# attiny4313_bo.net
KiCad netlist of a schematic drawn in EAGLE
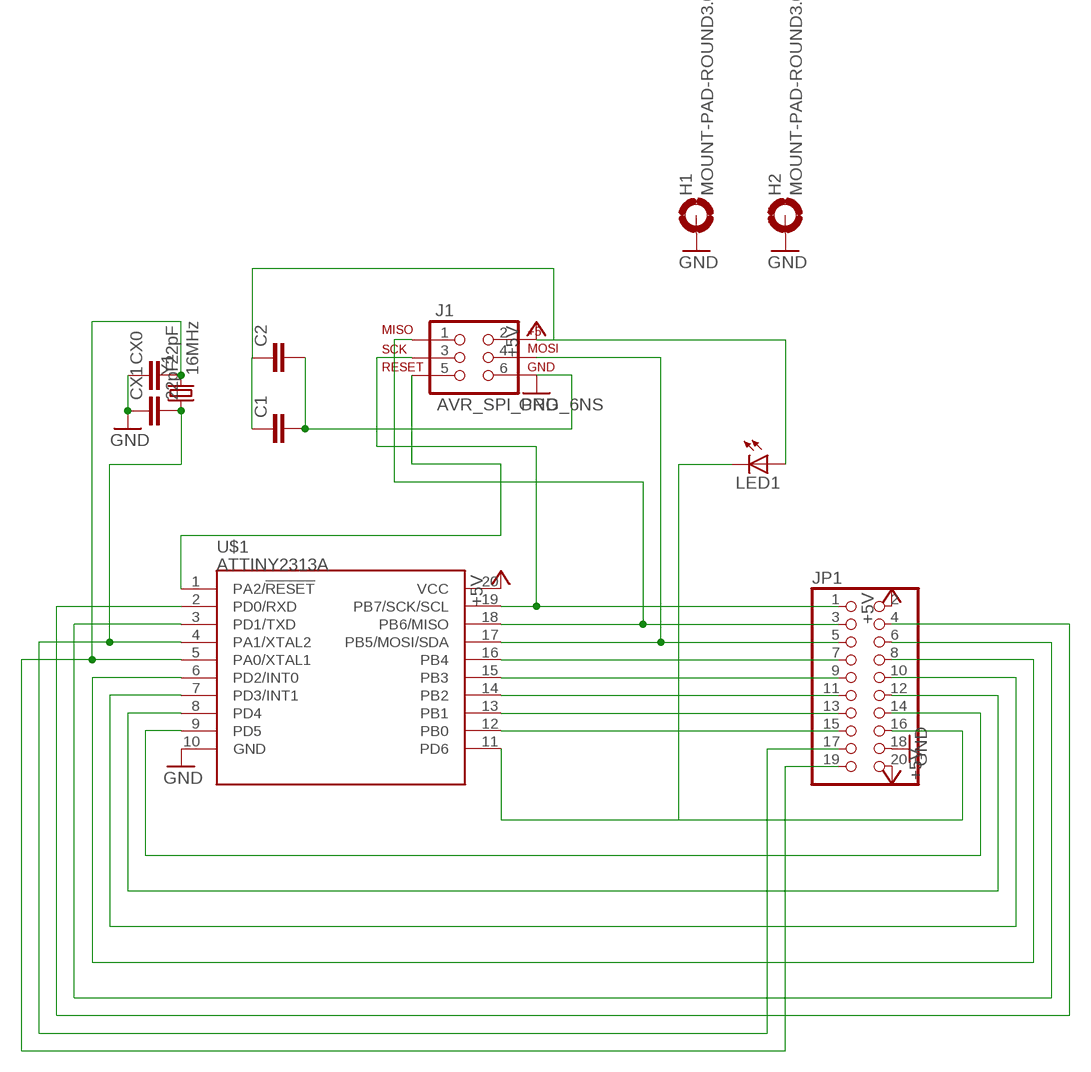
[diagram p0: schematic, sheet 1]

(export (version "E")
  (design (tool "Eeschema 10.0.6"))
  (components
    (comp (ref "C1")
      (value "C-EUC0805")
      (footprint "eagle-import:C0805")
      (libsource (lib "eagle-import") (part "C-EUC0805"))
    )
    (comp (ref "C2")
      (value "C-EUC0805")
      (footprint "eagle-import:C0805")
      (libsource (lib "eagle-import") (part "C-EUC0805"))
    )
    (comp (ref "CX0")
      (value "22pF")
      (footprint "eagle-import:C0603")
      (libsource (lib "eagle-import") (part "C-EUC0603"))
    )
    (comp (ref "CX1")
      (value "22pF")
      (footprint "eagle-import:C0603")
      (libsource (lib "eagle-import") (part "C-EUC0603"))
    )
    (comp (ref "H1")
      (value "MOUNT-PAD-ROUND3.0")
      (footprint "eagle-import:3,0-PAD")
      (libsource (lib "eagle-import") (part "MOUNT-PAD-ROUND3.0"))
    )
    (comp (ref "H2")
      (value "MOUNT-PAD-ROUND3.0")
      (footprint "eagle-import:3,0-PAD")
      (libsource (lib "eagle-import") (part "MOUNT-PAD-ROUND3.0"))
    )
    (comp (ref "J1")
      (value "AVR_SPI_PRG_6NS")
      (footprint "eagle-import:2X3-NS")
      (libsource (lib "eagle-import") (part "AVR_SPI_PRG_6NS"))
    )
    (comp (ref "JP1")
      (value "PINHD-2X10")
      (footprint "eagle-import:2X10")
      (libsource (lib "eagle-import") (part "PINHD-2X10"))
    )
    (comp (ref "LED1")
      (value "LED0603")
      (footprint "eagle-import:LED-0603")
      (libsource (lib "eagle-import") (part "LED0603"))
    )
    (comp (ref "U$1")
      (value "ATTINY2313A")
      (footprint "eagle-import:SOP20")
      (libsource (lib "eagle-import") (part "ATTINY2313A"))
    )
    (comp (ref "Y1")
      (value "16MHz")
      (footprint "eagle-import:CRYSTAL-SMD-5X3")
      (libsource (lib "eagle-import") (part "CRYSTAL5X3"))
    )
  )
  (nets
    (net (code "1") (name "+5V") (class "Default")
      (node (ref "C1") (pin "1") (pinfunction "1_1") (pintype "passive"))
      (node (ref "C2") (pin "1") (pinfunction "1_1") (pintype "passive"))
      (node (ref "J1") (pin "2") (pinfunction "2_2") (pintype "passive"))
      (node (ref "JP1") (pin "2") (pinfunction "2_2") (pintype "passive"))
      (node (ref "JP1") (pin "20") (pinfunction "20_20") (pintype "passive"))
      (node (ref "LED1") (pin "A") (pinfunction "A_A") (pintype "passive"))
      (node (ref "U$1") (pin "20") (pinfunction "VCC_20") (pintype "bidirectional"))
    )
    (net (code "2") (name "GND") (class "Default")
      (node (ref "C1") (pin "2") (pinfunction "2_2") (pintype "passive"))
      (node (ref "C2") (pin "2") (pinfunction "2_2") (pintype "passive"))
      (node (ref "CX0") (pin "1") (pinfunction "1_1") (pintype "passive"))
      (node (ref "CX1") (pin "1") (pinfunction "1_1") (pintype "passive"))
      (node (ref "H1") (pin "B3,0") (pinfunction "MOUNT_B3,0") (pintype "passive"))
      (node (ref "H2") (pin "B3,0") (pinfunction "MOUNT_B3,0") (pintype "passive"))
      (node (ref "J1") (pin "6") (pinfunction "6_6") (pintype "passive"))
      (node (ref "JP1") (pin "18") (pinfunction "18_18") (pintype "passive"))
      (node (ref "U$1") (pin "10") (pinfunction "GND_10") (pintype "bidirectional"))
    )
    (net (code "3") (name "Net-(U$1-PA0{slash}XTAL1)") (class "Default")
      (node (ref "CX0") (pin "2") (pinfunction "2_2") (pintype "passive"))
      (node (ref "JP1") (pin "19") (pinfunction "19_19") (pintype "passive"))
      (node (ref "U$1") (pin "5") (pinfunction "PA0/XTAL1_5") (pintype "bidirectional"))
      (node (ref "Y1") (pin "3") (pinfunction "2_3") (pintype "passive"))
    )
    (net (code "4") (name "Net-(U$1-PA1{slash}XTAL2)") (class "Default")
      (node (ref "CX1") (pin "2") (pinfunction "2_2") (pintype "passive"))
      (node (ref "JP1") (pin "17") (pinfunction "17_17") (pintype "passive"))
      (node (ref "U$1") (pin "4") (pinfunction "PA1/XTAL2_4") (pintype "bidirectional"))
      (node (ref "Y1") (pin "1") (pinfunction "1_1") (pintype "passive"))
    )
    (net (code "5") (name "Net-(U$1-PA2{slash}~{RESET})") (class "Default")
      (node (ref "J1") (pin "5") (pinfunction "5_5") (pintype "passive"))
      (node (ref "U$1") (pin "1") (pinfunction "PA2/~{RESET}_1") (pintype "bidirectional"))
    )
    (net (code "6") (name "Net-(U$1-PB0)") (class "Default")
      (node (ref "JP1") (pin "15") (pinfunction "15_15") (pintype "passive"))
      (node (ref "U$1") (pin "12") (pinfunction "PB0_12") (pintype "bidirectional"))
    )
    (net (code "7") (name "Net-(U$1-PB1)") (class "Default")
      (node (ref "JP1") (pin "13") (pinfunction "13_13") (pintype "passive"))
      (node (ref "U$1") (pin "13") (pinfunction "PB1_13") (pintype "bidirectional"))
    )
    (net (code "8") (name "Net-(U$1-PB2)") (class "Default")
      (node (ref "JP1") (pin "11") (pinfunction "11_11") (pintype "passive"))
      (node (ref "U$1") (pin "14") (pinfunction "PB2_14") (pintype "bidirectional"))
    )
    (net (code "9") (name "Net-(U$1-PB3)") (class "Default")
      (node (ref "JP1") (pin "9") (pinfunction "9_9") (pintype "passive"))
      (node (ref "U$1") (pin "15") (pinfunction "PB3_15") (pintype "bidirectional"))
    )
    (net (code "10") (name "Net-(U$1-PB4)") (class "Default")
      (node (ref "JP1") (pin "7") (pinfunction "7_7") (pintype "passive"))
      (node (ref "U$1") (pin "16") (pinfunction "PB4_16") (pintype "bidirectional"))
    )
    (net (code "11") (name "Net-(U$1-PB5{slash}MOSI{slash}SDA)") (class "Default")
      (node (ref "J1") (pin "4") (pinfunction "4_4") (pintype "passive"))
      (node (ref "JP1") (pin "5") (pinfunction "5_5") (pintype "passive"))
      (node (ref "U$1") (pin "17") (pinfunction "PB5/MOSI/SDA_17") (pintype "bidirectional"))
    )
    (net (code "12") (name "Net-(U$1-PB6{slash}MISO)") (class "Default")
      (node (ref "J1") (pin "1") (pinfunction "1_1") (pintype "passive"))
      (node (ref "JP1") (pin "3") (pinfunction "3_3") (pintype "passive"))
      (node (ref "U$1") (pin "18") (pinfunction "PB6/MISO_18") (pintype "bidirectional"))
    )
    (net (code "13") (name "Net-(U$1-PB7{slash}SCK{slash}SCL)") (class "Default")
      (node (ref "J1") (pin "3") (pinfunction "3_3") (pintype "passive"))
      (node (ref "JP1") (pin "1") (pinfunction "1_1") (pintype "passive"))
      (node (ref "U$1") (pin "19") (pinfunction "PB7/SCK/SCL_19") (pintype "bidirectional"))
    )
    (net (code "14") (name "Net-(U$1-PD0{slash}RXD)") (class "Default")
      (node (ref "JP1") (pin "4") (pinfunction "4_4") (pintype "passive"))
      (node (ref "U$1") (pin "2") (pinfunction "PD0/RXD_2") (pintype "bidirectional"))
    )
    (net (code "15") (name "Net-(U$1-PD1{slash}TXD)") (class "Default")
      (node (ref "JP1") (pin "6") (pinfunction "6_6") (pintype "passive"))
      (node (ref "U$1") (pin "3") (pinfunction "PD1/TXD_3") (pintype "bidirectional"))
    )
    (net (code "16") (name "Net-(U$1-PD2{slash}INT0)") (class "Default")
      (node (ref "JP1") (pin "8") (pinfunction "8_8") (pintype "passive"))
      (node (ref "U$1") (pin "6") (pinfunction "PD2/INT0_6") (pintype "bidirectional"))
    )
    (net (code "17") (name "Net-(U$1-PD3{slash}INT1)") (class "Default")
      (node (ref "JP1") (pin "10") (pinfunction "10_10") (pintype "passive"))
      (node (ref "U$1") (pin "7") (pinfunction "PD3/INT1_7") (pintype "bidirectional"))
    )
    (net (code "18") (name "Net-(U$1-PD4)") (class "Default")
      (node (ref "JP1") (pin "12") (pinfunction "12_12") (pintype "passive"))
      (node (ref "U$1") (pin "8") (pinfunction "PD4_8") (pintype "bidirectional"))
    )
    (net (code "19") (name "Net-(U$1-PD5)") (class "Default")
      (node (ref "JP1") (pin "14") (pinfunction "14_14") (pintype "passive"))
      (node (ref "U$1") (pin "9") (pinfunction "PD5_9") (pintype "bidirectional"))
    )
    (net (code "20") (name "Net-(U$1-PD6)") (class "Default")
      (node (ref "JP1") (pin "16") (pinfunction "16_16") (pintype "passive"))
      (node (ref "LED1") (pin "C") (pinfunction "C_C") (pintype "passive"))
      (node (ref "U$1") (pin "11") (pinfunction "PD6_11") (pintype "bidirectional"))
    )
  )
)
